# sensors.net
KiCad netlist of a schematic drawn in EAGLE
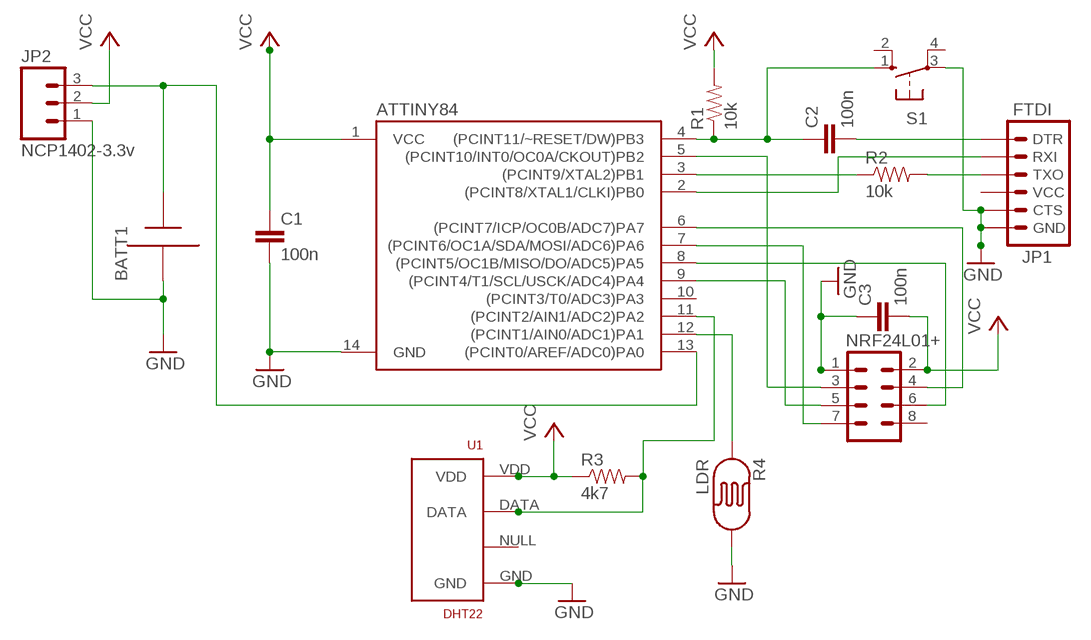
[diagram p0: schematic, sheet 1]

(export (version "E")
  (design (tool "Eeschema 10.0.6"))
  (components
    (comp (ref "ATTINY84")
      (value "ATTINY84ATTINY84-20PU")
      (footprint "eagle-import:DIL14")
      (libsource (lib "eagle-import") (part "ATTINY84ATTINY84-20PU"))
    )
    (comp (ref "BATT1")
      (value "AAA")
      (footprint "eagle-import:12BH412")
      (libsource (lib "eagle-import") (part "AAA"))
    )
    (comp (ref "C1")
      (value "100n")
      (footprint "eagle-import:CAP-PTH-5MM")
      (libsource (lib "eagle-import") (part "CAPPTH1"))
    )
    (comp (ref "C2")
      (value "100n")
      (footprint "eagle-import:CAP-PTH-5MM")
      (libsource (lib "eagle-import") (part "CAPPTH1"))
    )
    (comp (ref "C3")
      (value "100n")
      (footprint "eagle-import:CAP-PTH-5MM")
      (libsource (lib "eagle-import") (part "CAPPTH1"))
    )
    (comp (ref "JP1")
      (value "FTDI")
      (footprint "eagle-import:1X06")
      (libsource (lib "eagle-import") (part "ARDUINO_SERIAL_PROGRAMPTH"))
    )
    (comp (ref "JP2")
      (value "NCP1402-3.3v")
      (footprint "eagle-import:1X03")
      (libsource (lib "eagle-import") (part "M03PTH"))
    )
    (comp (ref "NRF24L01+")
      (value "M04X2")
      (footprint "eagle-import:2X4")
      (libsource (lib "eagle-import") (part "M04X2"))
    )
    (comp (ref "R1")
      (value "10k")
      (footprint "eagle-import:AXIAL-0.3EZ")
      (libsource (lib "eagle-import") (part "RESISTOREZ"))
    )
    (comp (ref "R2")
      (value "10k")
      (footprint "eagle-import:AXIAL-0.3EZ")
      (libsource (lib "eagle-import") (part "RESISTOREZ"))
    )
    (comp (ref "R3")
      (value "4k7")
      (footprint "eagle-import:AXIAL-0.3EZ")
      (libsource (lib "eagle-import") (part "RESISTOREZ"))
    )
    (comp (ref "R4")
      (value "LDR")
      (footprint "eagle-import:PHOTOCELL")
      (libsource (lib "eagle-import") (part "PHOTOCELLPTH"))
    )
    (comp (ref "S1")
      (value "10-XX")
      (footprint "eagle-import:B3F-10XX")
      (fields (field (name "MPN") "B3F-1000"))
      (libsource (lib "eagle-import") (part "10-XX"))
    )
    (comp (ref "U1")
      (value "DHT22")
      (footprint "eagle-import:RHT03_DHT-22")
      (libsource (lib "eagle-import") (part "RHT03_DHT-22_AM2302"))
    )
  )
  (nets
    (net (code "1") (name "GND") (class "Default")
      (node (ref "ATTINY84") (pin "14") (pinfunction "GND_14") (pintype "bidirectional"))
      (node (ref "BATT1") (pin "-") (pinfunction "-_-") (pintype "bidirectional"))
      (node (ref "C1") (pin "2") (pinfunction "2_2") (pintype "passive"))
      (node (ref "C3") (pin "1") (pinfunction "1_1") (pintype "passive"))
      (node (ref "JP1") (pin "5") (pinfunction "CTS_5") (pintype "passive"))
      (node (ref "JP1") (pin "6") (pinfunction "GND_6") (pintype "passive"))
      (node (ref "JP2") (pin "1") (pinfunction "1_1") (pintype "passive"))
      (node (ref "NRF24L01+") (pin "1") (pinfunction "1_1") (pintype "passive"))
      (node (ref "R4") (pin "2") (pinfunction "P$2_2") (pintype "bidirectional"))
      (node (ref "S1") (pin "3") (pinfunction "P_3") (pintype "passive"))
      (node (ref "U1") (pin "GND") (pinfunction "GND_GND") (pintype "power_in"))
    )
    (net (code "2") (name "Net-(ATTINY84-(PCINT0{slash}AREF{slash}ADC0)PA0)") (class "Default")
      (node (ref "ATTINY84") (pin "13") (pinfunction "(PCINT0/AREF/ADC0)PA0_13") (pintype "bidirectional"))
      (node (ref "BATT1") (pin "+") (pinfunction "+_+") (pintype "bidirectional"))
      (node (ref "JP2") (pin "3") (pinfunction "3_3") (pintype "passive"))
    )
    (net (code "3") (name "Net-(ATTINY84-(PCINT1{slash}AIN0{slash}ADC1)PA1)") (class "Default")
      (node (ref "ATTINY84") (pin "12") (pinfunction "(PCINT1/AIN0/ADC1)PA1_12") (pintype "bidirectional"))
      (node (ref "R4") (pin "1") (pinfunction "P$1_1") (pintype "bidirectional"))
    )
    (net (code "4") (name "Net-(ATTINY84-(PCINT2{slash}AIN1{slash}ADC2)PA2)") (class "Default")
      (node (ref "ATTINY84") (pin "11") (pinfunction "(PCINT2/AIN1/ADC2)PA2_11") (pintype "bidirectional"))
      (node (ref "R3") (pin "P$2") (pinfunction "2_P$2") (pintype "passive"))
      (node (ref "U1") (pin "DATA") (pinfunction "DATA_DATA") (pintype "bidirectional"))
    )
    (net (code "5") (name "Net-(ATTINY84-(PCINT4{slash}T1{slash}SCL{slash}USCK{slash}ADC4)PA4)") (class "Default")
      (node (ref "ATTINY84") (pin "9") (pinfunction "(PCINT4/T1/SCL/USCK/ADC4)PA4_9") (pintype "bidirectional"))
      (node (ref "NRF24L01+") (pin "5") (pinfunction "5_5") (pintype "passive"))
    )
    (net (code "6") (name "Net-(ATTINY84-(PCINT5{slash}OC1B{slash}MISO{slash}DO{slash}ADC5)PA5)") (class "Default")
      (node (ref "ATTINY84") (pin "8") (pinfunction "(PCINT5/OC1B/MISO/DO/ADC5)PA5_8") (pintype "bidirectional"))
      (node (ref "NRF24L01+") (pin "6") (pinfunction "6_6") (pintype "passive"))
    )
    (net (code "7") (name "Net-(ATTINY84-(PCINT6{slash}OC1A{slash}SDA{slash}MOSI{slash}ADC6)PA6)") (class "Default")
      (node (ref "ATTINY84") (pin "7") (pinfunction "(PCINT6/OC1A/SDA/MOSI/ADC6)PA6_7") (pintype "bidirectional"))
      (node (ref "NRF24L01+") (pin "7") (pinfunction "7_7") (pintype "passive"))
    )
    (net (code "8") (name "Net-(ATTINY84-(PCINT7{slash}ICP{slash}OC0B{slash}ADC7)PA7)") (class "Default")
      (node (ref "ATTINY84") (pin "6") (pinfunction "(PCINT7/ICP/OC0B/ADC7)PA7_6") (pintype "bidirectional"))
      (node (ref "NRF24L01+") (pin "4") (pinfunction "4_4") (pintype "passive"))
    )
    (net (code "9") (name "Net-(ATTINY84-(PCINT8{slash}XTAL1{slash}CLKI)PB0)") (class "Default")
      (node (ref "ATTINY84") (pin "2") (pinfunction "(PCINT8/XTAL1/CLKI)PB0_2") (pintype "bidirectional"))
      (node (ref "JP1") (pin "2") (pinfunction "RXI_2") (pintype "passive"))
    )
    (net (code "10") (name "Net-(ATTINY84-(PCINT9{slash}XTAL2)PB1)") (class "Default")
      (node (ref "ATTINY84") (pin "3") (pinfunction "(PCINT9/XTAL2)PB1_3") (pintype "bidirectional"))
      (node (ref "R2") (pin "P$1") (pinfunction "1_P$1") (pintype "passive"))
    )
    (net (code "11") (name "Net-(ATTINY84-(PCINT10{slash}INT0{slash}OC0A{slash}CKOUT)PB2)") (class "Default")
      (node (ref "ATTINY84") (pin "5") (pinfunction "(PCINT10/INT0/OC0A/CKOUT)PB2_5") (pintype "bidirectional"))
      (node (ref "NRF24L01+") (pin "3") (pinfunction "3_3") (pintype "passive"))
    )
    (net (code "12") (name "Net-(ATTINY84-(PCINT11{slash}~{RESET{slash}DW})PB3)") (class "Default")
      (node (ref "ATTINY84") (pin "4") (pinfunction "(PCINT11/~{RESET/DW})PB3_4") (pintype "bidirectional"))
      (node (ref "C2") (pin "1") (pinfunction "1_1") (pintype "passive"))
      (node (ref "R1") (pin "P$1") (pinfunction "1_P$1") (pintype "passive"))
      (node (ref "S1") (pin "1") (pinfunction "S_1") (pintype "passive"))
    )
    (net (code "13") (name "Net-(JP1-DTR)") (class "Default")
      (node (ref "C2") (pin "2") (pinfunction "2_2") (pintype "passive"))
      (node (ref "JP1") (pin "1") (pinfunction "DTR_1") (pintype "passive"))
    )
    (net (code "14") (name "Net-(JP1-TXO)") (class "Default")
      (node (ref "JP1") (pin "3") (pinfunction "TXO_3") (pintype "passive"))
      (node (ref "R2") (pin "P$2") (pinfunction "2_P$2") (pintype "passive"))
    )
    (net (code "15") (name "VCC") (class "Default")
      (node (ref "ATTINY84") (pin "1") (pinfunction "VCC_1") (pintype "bidirectional"))
      (node (ref "C1") (pin "1") (pinfunction "1_1") (pintype "passive"))
      (node (ref "C3") (pin "2") (pinfunction "2_2") (pintype "passive"))
      (node (ref "JP2") (pin "2") (pinfunction "2_2") (pintype "passive"))
      (node (ref "NRF24L01+") (pin "2") (pinfunction "2_2") (pintype "passive"))
      (node (ref "R1") (pin "P$2") (pinfunction "2_P$2") (pintype "passive"))
      (node (ref "R3") (pin "P$1") (pinfunction "1_P$1") (pintype "passive"))
      (node (ref "U1") (pin "VDD") (pinfunction "VDD_VDD") (pintype "power_in"))
    )
    (net (code "16") (name "unconnected-(ATTINY84-(PCINT3{slash}T0{slash}ADC3)PA3-Pad10)") (class "Default")
      (node (ref "ATTINY84") (pin "10") (pinfunction "(PCINT3/T0/ADC3)PA3_10") (pintype "bidirectional"))
    )
    (net (code "17") (name "unconnected-(JP1-VCC-Pad4)") (class "Default")
      (node (ref "JP1") (pin "4") (pinfunction "VCC_4") (pintype "passive"))
    )
    (net (code "18") (name "unconnected-(NRF24L01+-Pad8)") (class "Default")
      (node (ref "NRF24L01+") (pin "8") (pinfunction "8_8") (pintype "passive"))
    )
    (net (code "19") (name "unconnected-(S1-P1-Pad4)") (class "Default")
      (node (ref "S1") (pin "4") (pinfunction "P1_4") (pintype "passive"))
    )
    (net (code "20") (name "unconnected-(S1-S1-Pad2)") (class "Default")
      (node (ref "S1") (pin "2") (pinfunction "S1_2") (pintype "passive"))
    )
    (net (code "21") (name "unconnected-(U1-PadNULL)") (class "Default")
      (node (ref "U1") (pin "NULL") (pinfunction "NULL_NULL") (pintype "no_connect"))
    )
  )
)
